# BUZZER.net
KiCad netlist of a schematic drawn in EAGLE
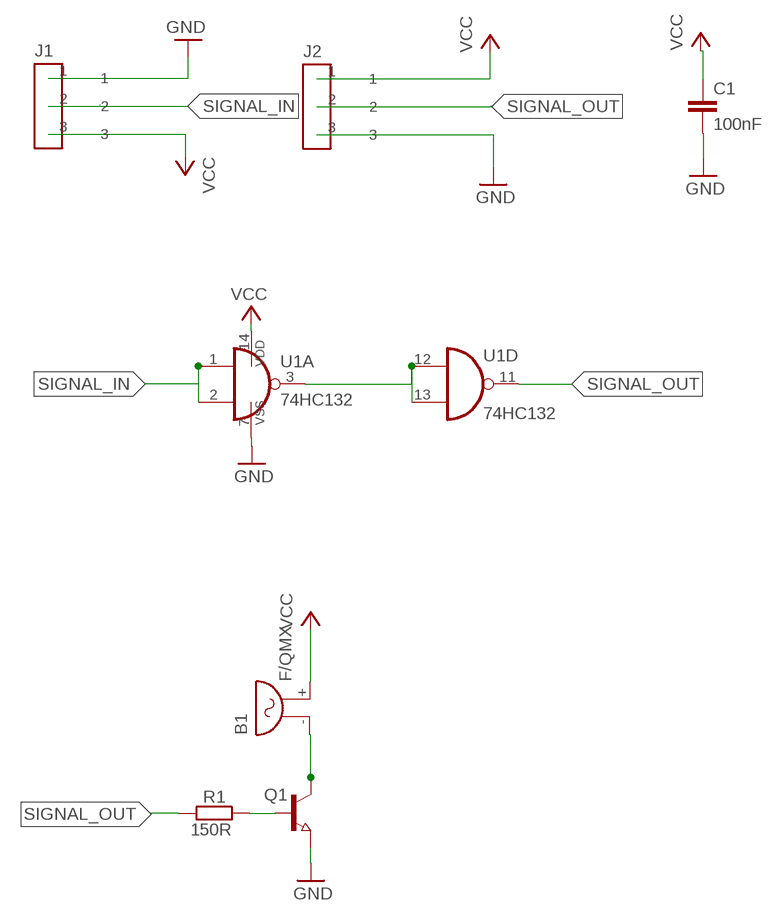
[diagram p0: schematic, sheet 1]

(export (version "E")
  (design (tool "Eeschema 10.0.6"))
  (components
    (comp (ref "B1")
      (value "F/QMX")
      (footprint "eagle-import:F_QMX")
      (libsource (lib "eagle-import") (part "F/QMX"))
    )
    (comp (ref "C1")
      (value "100nF")
      (footprint "eagle-import:C0805")
      (libsource (lib "eagle-import") (part "C-EUC0805"))
    )
    (comp (ref "J1")
      (value "CONECTOR_MACHO")
      (footprint "eagle-import:MALE")
      (libsource (lib "eagle-import") (part "CONECTOR_MACHO"))
    )
    (comp (ref "J2")
      (value "CONECTOR_FEMEA")
      (footprint "eagle-import:FEMALE")
      (libsource (lib "eagle-import") (part "CONECTOR_FEMEA"))
    )
    (comp (ref "Q1")
      (value "BC817")
      (footprint "eagle-import:SOT23")
      (libsource (lib "eagle-import") (part "NPN-TRANSISTOR_SOT23"))
    )
    (comp (ref "R1")
      (value "150R")
      (footprint "eagle-import:R0805W")
      (libsource (lib "eagle-import") (part "R-EU_R0805W"))
    )
    (comp (ref "U1")
      (value "74HC132")
      (footprint "eagle-import:SO14")
      (libsource (lib "eagle-import") (part "4011D"))
    )
  )
  (nets
    (net (code "1") (name "GND") (class "Default")
      (node (ref "C1") (pin "2") (pinfunction "2_2") (pintype "passive"))
      (node (ref "J1") (pin "1") (pinfunction "1_1") (pintype "bidirectional"))
      (node (ref "J2") (pin "3") (pinfunction "3_3") (pintype "bidirectional"))
      (node (ref "Q1") (pin "2") (pinfunction "E_2") (pintype "passive"))
      (node (ref "U1") (pin "7") (pinfunction "VSS_7") (pintype "power_in"))
    )
    (net (code "2") (name "Net-(B1-1)") (class "Default")
      (node (ref "B1") (pin "-") (pinfunction "1_-") (pintype "passive"))
      (node (ref "Q1") (pin "3") (pinfunction "C_3") (pintype "passive"))
    )
    (net (code "3") (name "Net-(Q1-B)") (class "Default")
      (node (ref "Q1") (pin "1") (pinfunction "B_1") (pintype "passive"))
      (node (ref "R1") (pin "1") (pinfunction "1_1") (pintype "passive"))
    )
    (net (code "4") (name "Net-(U1A-O)") (class "Default")
      (node (ref "U1") (pin "12") (pinfunction "I0_12") (pintype "input"))
      (node (ref "U1") (pin "13") (pinfunction "I1_13") (pintype "input"))
      (node (ref "U1") (pin "3") (pinfunction "O_3") (pintype "output"))
    )
    (net (code "5") (name "SIGNAL_IN") (class "Default")
      (node (ref "J1") (pin "2") (pinfunction "2_2") (pintype "bidirectional"))
      (node (ref "U1") (pin "1") (pinfunction "I0_1") (pintype "input"))
      (node (ref "U1") (pin "2") (pinfunction "I1_2") (pintype "input"))
    )
    (net (code "6") (name "SIGNAL_OUT") (class "Default")
      (node (ref "J2") (pin "2") (pinfunction "2_2") (pintype "bidirectional"))
      (node (ref "R1") (pin "2") (pinfunction "2_2") (pintype "passive"))
      (node (ref "U1") (pin "11") (pinfunction "O_11") (pintype "output"))
    )
    (net (code "7") (name "VCC") (class "Default")
      (node (ref "B1") (pin "+") (pinfunction "2_+") (pintype "passive"))
      (node (ref "C1") (pin "1") (pinfunction "1_1") (pintype "passive"))
      (node (ref "J1") (pin "3") (pinfunction "3_3") (pintype "bidirectional"))
      (node (ref "J2") (pin "1") (pinfunction "1_1") (pintype "bidirectional"))
      (node (ref "U1") (pin "14") (pinfunction "VDD_14") (pintype "power_in"))
    )
  )
)
